# beer-pong.net
KiCad netlist of a schematic drawn in EAGLE
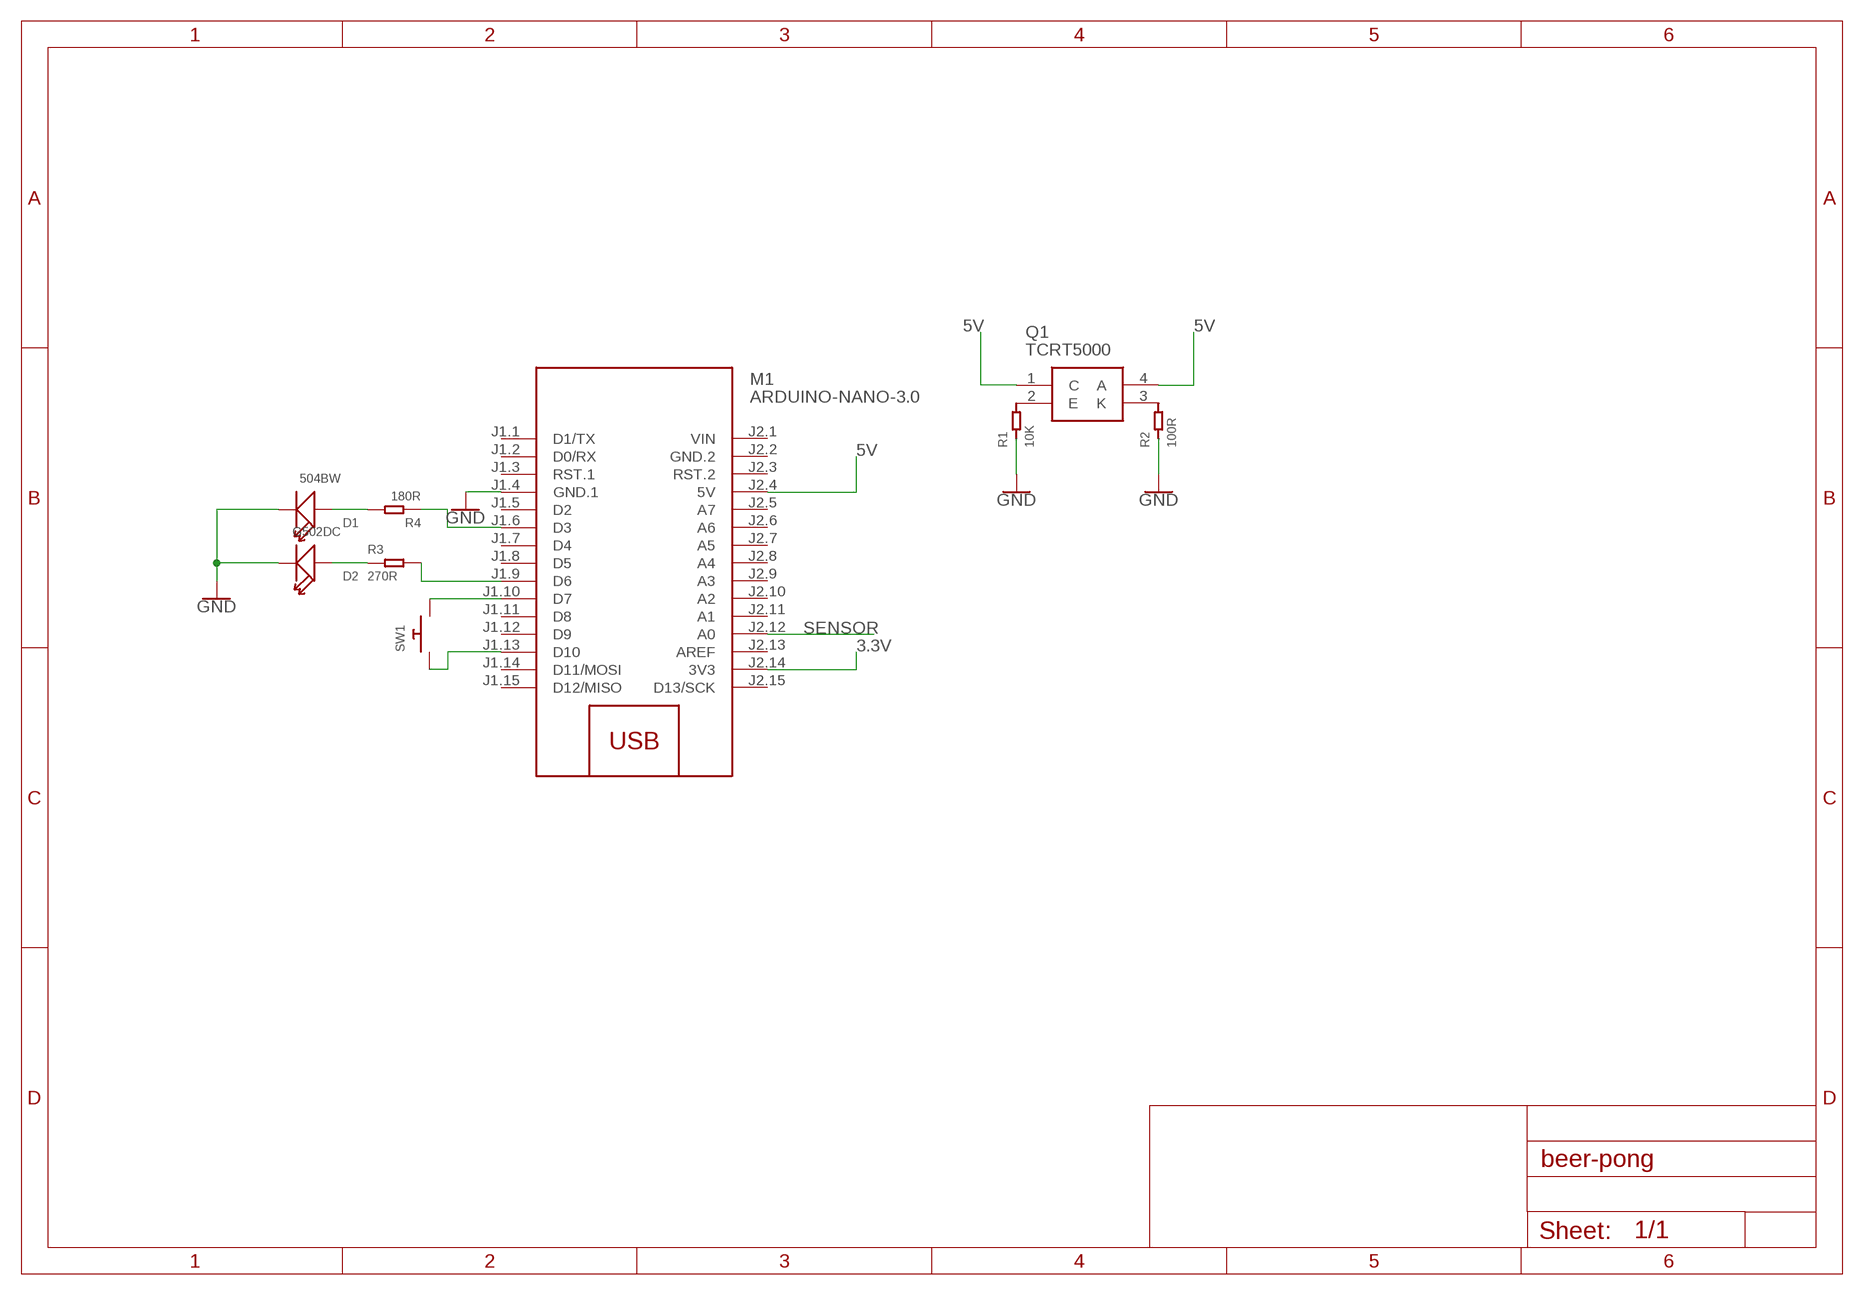
[diagram p0: schematic, sheet 1]

(export (version "E")
  (design (tool "Eeschema 10.0.6"))
  (components
    (comp (ref "D1")
      (value "504BW")
      (footprint "eagle-import:LED2-2.54-D5.0MM")
      (libsource (lib "eagle-import") (part "DIP-LED-BLUE-BLUE(2P-D5MM)"))
    )
    (comp (ref "D2")
      (value "G502DC")
      (footprint "eagle-import:LED2-2.54-D5.0MM")
      (libsource (lib "eagle-import") (part "DIP-LED-GREEN-GREEN(2P-D5MM)"))
    )
    (comp (ref "M1")
      (value "ARDUINO-NANO-3.0")
      (footprint "eagle-import:ARDUINO-NANO-3.0")
      (libsource (lib "eagle-import") (part "ARDUINO-NANO-3.0"))
    )
    (comp (ref "Q1")
      (value "TCRT5000")
      (footprint "eagle-import:TCRT5000")
      (fields (field (name "MOUSER_PART_NUMBER") "782-TCRT5000") (field (name "RS_PART_NUMBER") "7085017P"))
      (libsource (lib "eagle-import") (part "TCRT5000"))
    )
    (comp (ref "R1")
      (value "10K")
      (footprint "eagle-import:PR-D2.3XL6.5MM")
      (fields (field (name "MPN") "FHCFR-1/4W-103J"))
      (libsource (lib "eagle-import") (part "DIP-RES-10K-5%-1/4W(PR-D2.3XL6.5MM)"))
    )
    (comp (ref "R2")
      (value "100R")
      (footprint "eagle-import:PR-D2.3XL6.5MM")
      (fields (field (name "MPN") "FHCFR-1/4W-101J"))
      (libsource (lib "eagle-import") (part "DIP-RES-100R-5%-1/4W(PR-D2.3XL6.5MM)"))
    )
    (comp (ref "R3")
      (value "270R")
      (footprint "eagle-import:PR-D2.3XL6.5MM")
      (fields (field (name "MPN") "FHCFR-1/4W-221J"))
      (libsource (lib "eagle-import") (part "DIP-RES-220R-5%-1/4W(PR-D2.3XL6.5MM)"))
    )
    (comp (ref "R4")
      (value "180R")
      (footprint "eagle-import:PR-D2.3XL6.5MM")
      (fields (field (name "MPN") "FHCFR-1/4W-221J"))
      (libsource (lib "eagle-import") (part "DIP-RES-220R-5%-1/4W(PR-D2.3XL6.5MM)"))
    )
    (comp (ref "SW1")
      (value "SWITCH_PUSHBUTTONEVQ-PE")
      (footprint "eagle-import:TACT_PANA-EVQ")
      (libsource (lib "eagle-import") (part "SWITCH_PUSHBUTTONEVQ-PE"))
    )
  )
  (nets
    (net (code "1") (name "/3.3V") (class "Default")
      (node (ref "M1") (pin "J2.14") (pinfunction "3V3_J2.14") (pintype "power_in"))
    )
    (net (code "2") (name "/5V") (class "Default")
      (node (ref "M1") (pin "J2.4") (pinfunction "5V_J2.4") (pintype "power_in"))
      (node (ref "Q1") (pin "1") (pinfunction "C_1") (pintype "bidirectional"))
      (node (ref "Q1") (pin "4") (pinfunction "A_4") (pintype "bidirectional"))
    )
    (net (code "3") (name "/GND.2") (class "Default")
      (node (ref "M1") (pin "J2.2") (pinfunction "GND.2_J2.2") (pintype "power_in"))
    )
    (net (code "4") (name "/SENSOR") (class "Default")
      (node (ref "M1") (pin "J2.12") (pinfunction "A0_J2.12") (pintype "bidirectional"))
    )
    (net (code "5") (name "/VIN") (class "Default")
      (node (ref "M1") (pin "J2.1") (pinfunction "VIN_J2.1") (pintype "power_in"))
    )
    (net (code "6") (name "GND") (class "Default")
      (node (ref "D1") (pin "-") (pinfunction "-_-") (pintype "passive"))
      (node (ref "D2") (pin "-") (pinfunction "-_-") (pintype "passive"))
      (node (ref "M1") (pin "J1.4") (pinfunction "GND.1_J1.4") (pintype "power_in"))
      (node (ref "R1") (pin "1") (pinfunction "1_1") (pintype "passive"))
      (node (ref "R2") (pin "1") (pinfunction "1_1") (pintype "passive"))
    )
    (net (code "7") (name "Net-(D1-Pad+)") (class "Default")
      (node (ref "D1") (pin "+") (pinfunction "+_+") (pintype "passive"))
      (node (ref "R4") (pin "2") (pinfunction "2_2") (pintype "passive"))
    )
    (net (code "8") (name "Net-(D2-Pad+)") (class "Default")
      (node (ref "D2") (pin "+") (pinfunction "+_+") (pintype "passive"))
      (node (ref "R3") (pin "1") (pinfunction "1_1") (pintype "passive"))
    )
    (net (code "9") (name "Net-(M1-D3)") (class "Default")
      (node (ref "M1") (pin "J1.6") (pinfunction "D3_J1.6") (pintype "bidirectional"))
      (node (ref "R4") (pin "1") (pinfunction "1_1") (pintype "passive"))
    )
    (net (code "10") (name "Net-(M1-D6)") (class "Default")
      (node (ref "M1") (pin "J1.9") (pinfunction "D6_J1.9") (pintype "bidirectional"))
      (node (ref "R3") (pin "2") (pinfunction "2_2") (pintype "passive"))
    )
    (net (code "11") (name "Net-(M1-D7)") (class "Default")
      (node (ref "M1") (pin "J1.10") (pinfunction "D7_J1.10") (pintype "bidirectional"))
      (node (ref "SW1") (pin "P$2") (pinfunction "P$2_P$2") (pintype "passive"))
    )
    (net (code "12") (name "Net-(M1-D10)") (class "Default")
      (node (ref "M1") (pin "J1.13") (pinfunction "D10_J1.13") (pintype "bidirectional"))
      (node (ref "SW1") (pin "P$1") (pinfunction "P$1_P$1") (pintype "passive"))
    )
    (net (code "13") (name "Net-(Q1-E)") (class "Default")
      (node (ref "Q1") (pin "2") (pinfunction "E_2") (pintype "bidirectional"))
      (node (ref "R1") (pin "2") (pinfunction "2_2") (pintype "passive"))
    )
    (net (code "14") (name "Net-(Q1-K)") (class "Default")
      (node (ref "Q1") (pin "3") (pinfunction "K_3") (pintype "bidirectional"))
      (node (ref "R2") (pin "2") (pinfunction "2_2") (pintype "passive"))
    )
    (net (code "15") (name "unconnected-(M1-A1-PadJ2.11)") (class "Default")
      (node (ref "M1") (pin "J2.11") (pinfunction "A1_J2.11") (pintype "bidirectional"))
    )
    (net (code "16") (name "unconnected-(M1-A2-PadJ2.10)") (class "Default")
      (node (ref "M1") (pin "J2.10") (pinfunction "A2_J2.10") (pintype "bidirectional"))
    )
    (net (code "17") (name "unconnected-(M1-A3-PadJ2.9)") (class "Default")
      (node (ref "M1") (pin "J2.9") (pinfunction "A3_J2.9") (pintype "bidirectional"))
    )
    (net (code "18") (name "unconnected-(M1-A4-PadJ2.8)") (class "Default")
      (node (ref "M1") (pin "J2.8") (pinfunction "A4_J2.8") (pintype "bidirectional"))
    )
    (net (code "19") (name "unconnected-(M1-A5-PadJ2.7)") (class "Default")
      (node (ref "M1") (pin "J2.7") (pinfunction "A5_J2.7") (pintype "bidirectional"))
    )
    (net (code "20") (name "unconnected-(M1-A6-PadJ2.6)") (class "Default")
      (node (ref "M1") (pin "J2.6") (pinfunction "A6_J2.6") (pintype "bidirectional"))
    )
    (net (code "21") (name "unconnected-(M1-A7-PadJ2.5)") (class "Default")
      (node (ref "M1") (pin "J2.5") (pinfunction "A7_J2.5") (pintype "bidirectional"))
    )
    (net (code "22") (name "unconnected-(M1-AREF-PadJ2.13)") (class "Default")
      (node (ref "M1") (pin "J2.13") (pinfunction "AREF_J2.13") (pintype "bidirectional"))
    )
    (net (code "23") (name "unconnected-(M1-D0{slash}RX-PadJ1.2)") (class "Default")
      (node (ref "M1") (pin "J1.2") (pinfunction "D0/RX_J1.2") (pintype "bidirectional"))
    )
    (net (code "24") (name "unconnected-(M1-D1{slash}TX-PadJ1.1)") (class "Default")
      (node (ref "M1") (pin "J1.1") (pinfunction "D1/TX_J1.1") (pintype "bidirectional"))
    )
    (net (code "25") (name "unconnected-(M1-D2-PadJ1.5)") (class "Default")
      (node (ref "M1") (pin "J1.5") (pinfunction "D2_J1.5") (pintype "bidirectional"))
    )
    (net (code "26") (name "unconnected-(M1-D4-PadJ1.7)") (class "Default")
      (node (ref "M1") (pin "J1.7") (pinfunction "D4_J1.7") (pintype "bidirectional"))
    )
    (net (code "27") (name "unconnected-(M1-D5-PadJ1.8)") (class "Default")
      (node (ref "M1") (pin "J1.8") (pinfunction "D5_J1.8") (pintype "bidirectional"))
    )
    (net (code "28") (name "unconnected-(M1-D8-PadJ1.11)") (class "Default")
      (node (ref "M1") (pin "J1.11") (pinfunction "D8_J1.11") (pintype "bidirectional"))
    )
    (net (code "29") (name "unconnected-(M1-D9-PadJ1.12)") (class "Default")
      (node (ref "M1") (pin "J1.12") (pinfunction "D9_J1.12") (pintype "bidirectional"))
    )
    (net (code "30") (name "unconnected-(M1-D11{slash}MOSI-PadJ1.14)") (class "Default")
      (node (ref "M1") (pin "J1.14") (pinfunction "D11/MOSI_J1.14") (pintype "bidirectional"))
    )
    (net (code "31") (name "unconnected-(M1-D12{slash}MISO-PadJ1.15)") (class "Default")
      (node (ref "M1") (pin "J1.15") (pinfunction "D12/MISO_J1.15") (pintype "bidirectional"))
    )
    (net (code "32") (name "unconnected-(M1-D13{slash}SCK-PadJ2.15)") (class "Default")
      (node (ref "M1") (pin "J2.15") (pinfunction "D13/SCK_J2.15") (pintype "bidirectional"))
    )
    (net (code "33") (name "unconnected-(M1-RST.1-PadJ1.3)") (class "Default")
      (node (ref "M1") (pin "J1.3") (pinfunction "RST.1_J1.3") (pintype "bidirectional"))
    )
    (net (code "34") (name "unconnected-(M1-RST.2-PadJ2.3)") (class "Default")
      (node (ref "M1") (pin "J2.3") (pinfunction "RST.2_J2.3") (pintype "bidirectional"))
    )
  )
)
